# Connectors.net
KiCad netlist of a schematic drawn in Altium Designer
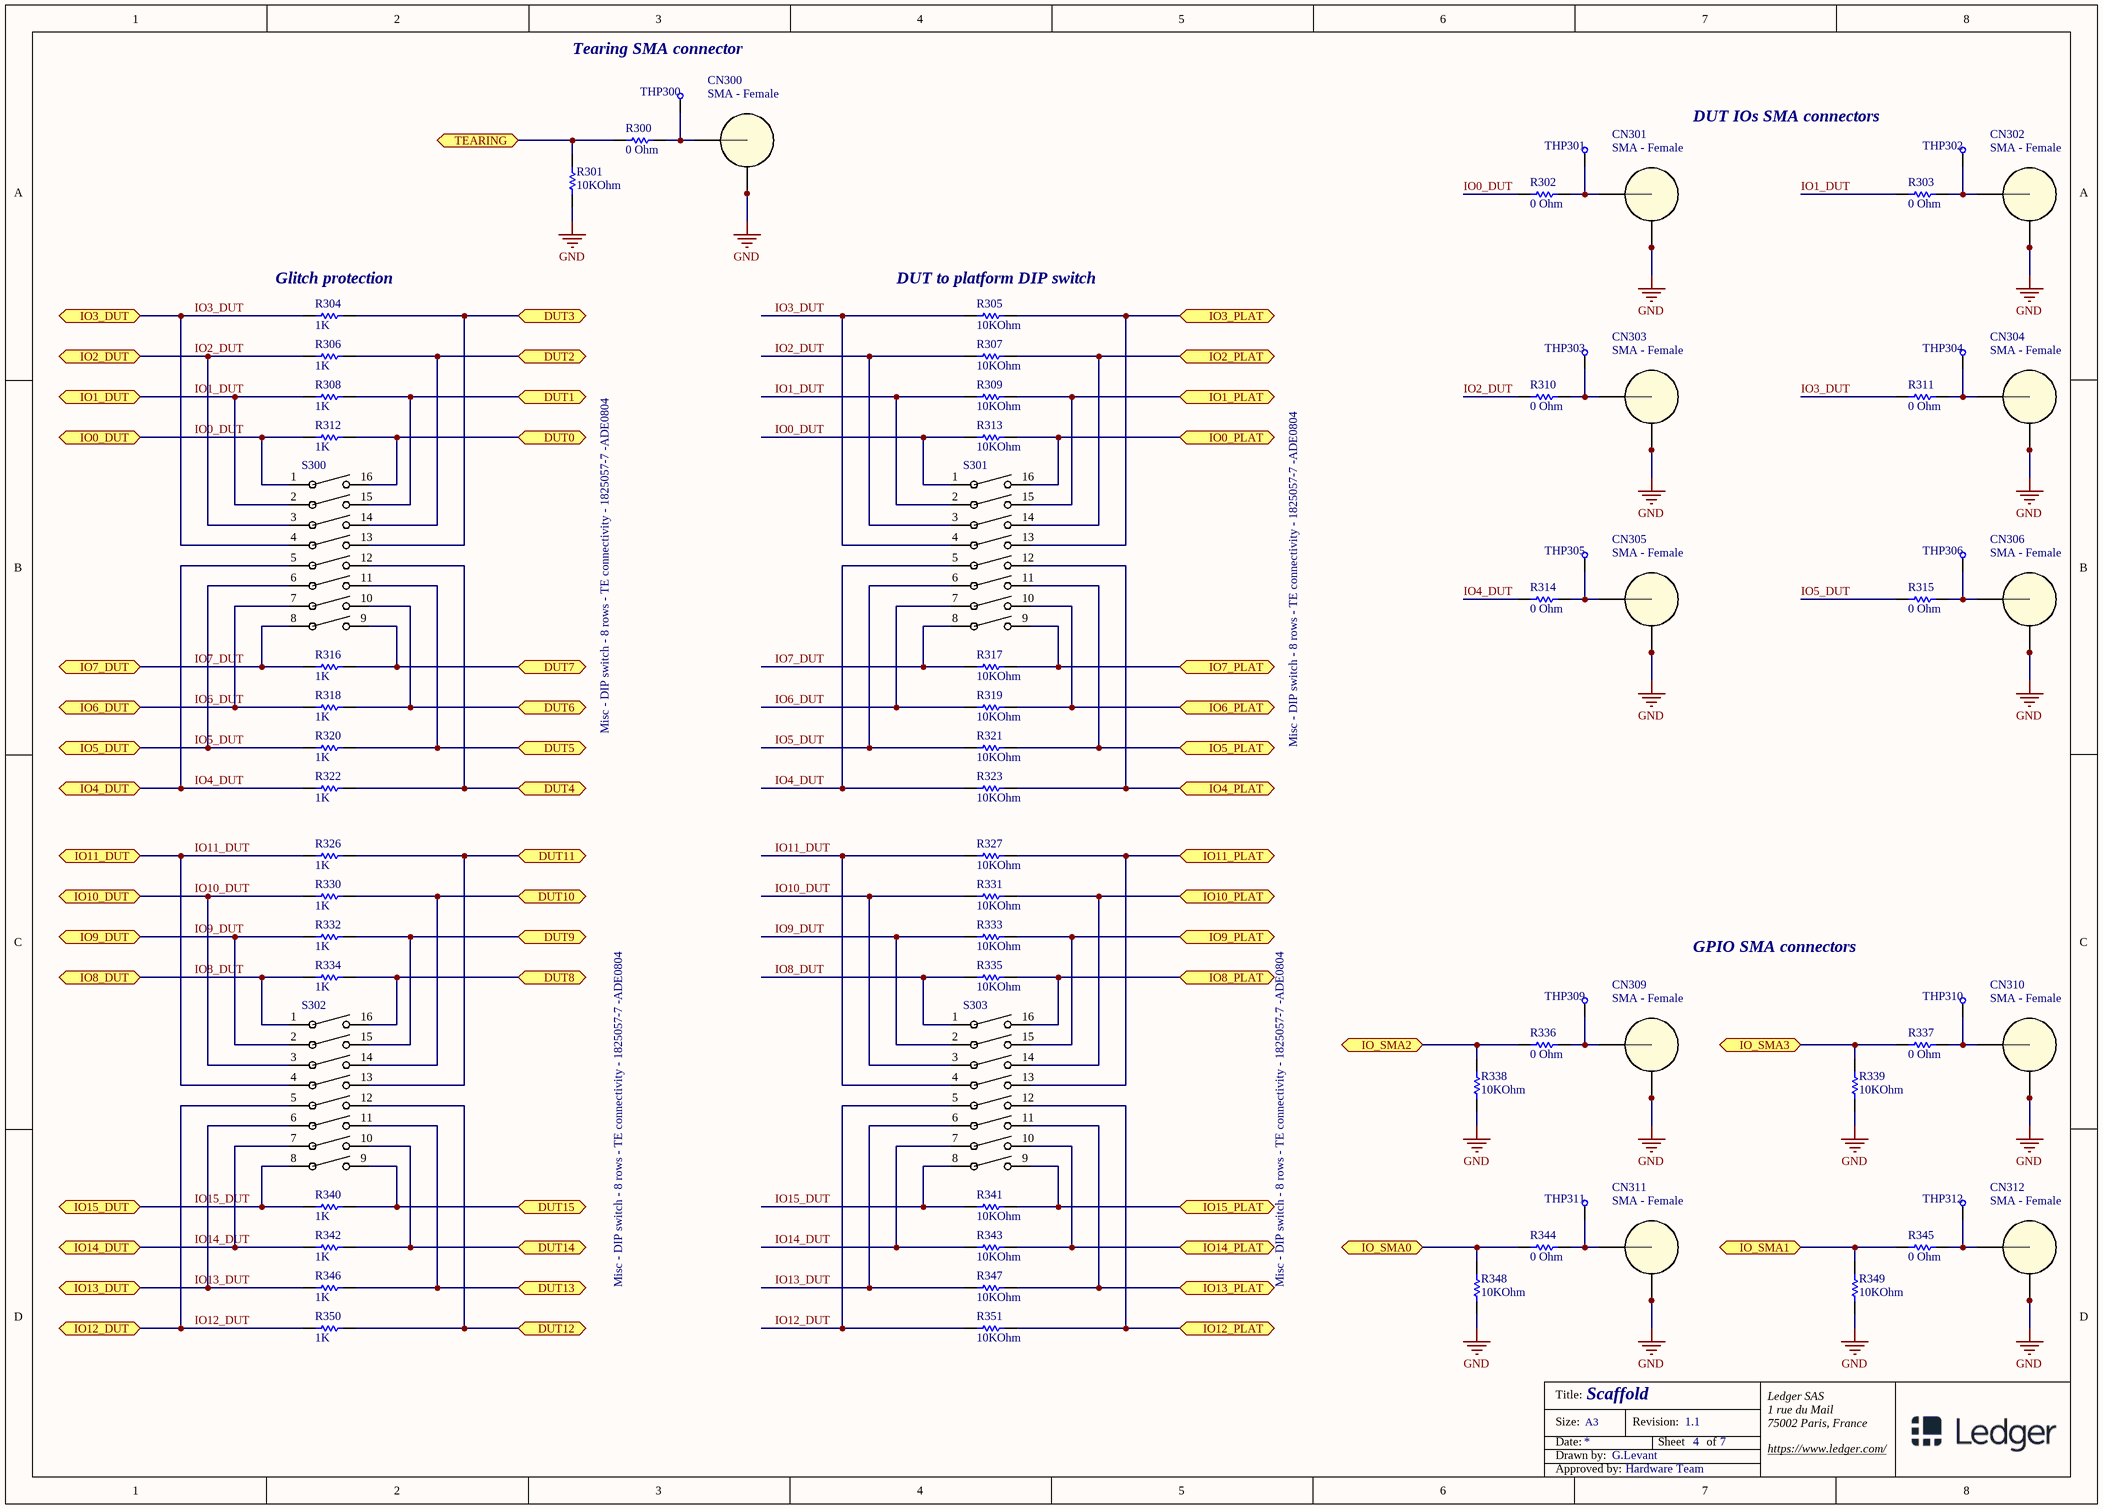
[diagram p0: Connectors.SchDoc]

(export (version "E")
  (design (tool "Eeschema 10.0.6"))
  (components
    (comp (ref "CN300")
      (value "SMA - Female")
      (footprint "SAMTEC_SMA-J-P-X-ST-EM3")
      (description "Connector - SMA - Female - Horizontal - Mid Mount - Samtec - SMA–J–P–H–ST–EM3")
      (fields (field (name "MANUFACTURER") "Samtec"))
      (libsource (lib "Ledger_Dev") (part "Connector - SMA - Female - Horizontal - Mid Mount - Samtec - SMA–J–P–H–ST–EM3"))
    )
    (comp (ref "CN301")
      (value "SMA - Female")
      (footprint "SAMTEC_SMA-J-P-X-ST-EM3")
      (description "Connector - SMA - Female - Horizontal - Mid Mount - Samtec - SMA–J–P–H–ST–EM3")
      (fields (field (name "MANUFACTURER") "Samtec"))
      (libsource (lib "Ledger_Dev") (part "Connector - SMA - Female - Horizontal - Mid Mount - Samtec - SMA–J–P–H–ST–EM3"))
    )
    (comp (ref "CN302")
      (value "SMA - Female")
      (footprint "SAMTEC_SMA-J-P-X-ST-EM3")
      (description "Connector - SMA - Female - Horizontal - Mid Mount - Samtec - SMA–J–P–H–ST–EM3")
      (fields (field (name "MANUFACTURER") "Samtec"))
      (libsource (lib "Ledger_Dev") (part "Connector - SMA - Female - Horizontal - Mid Mount - Samtec - SMA–J–P–H–ST–EM3"))
    )
    (comp (ref "CN303")
      (value "SMA - Female")
      (footprint "SAMTEC_SMA-J-P-X-ST-EM3")
      (description "Connector - SMA - Female - Horizontal - Mid Mount - Samtec - SMA–J–P–H–ST–EM3")
      (fields (field (name "MANUFACTURER") "Samtec"))
      (libsource (lib "Ledger_Dev") (part "Connector - SMA - Female - Horizontal - Mid Mount - Samtec - SMA–J–P–H–ST–EM3"))
    )
    (comp (ref "CN304")
      (value "SMA - Female")
      (footprint "SAMTEC_SMA-J-P-X-ST-EM3")
      (description "Connector - SMA - Female - Horizontal - Mid Mount - Samtec - SMA–J–P–H–ST–EM3")
      (fields (field (name "MANUFACTURER") "Samtec"))
      (libsource (lib "Ledger_Dev") (part "Connector - SMA - Female - Horizontal - Mid Mount - Samtec - SMA–J–P–H–ST–EM3"))
    )
    (comp (ref "CN305")
      (value "SMA - Female")
      (footprint "SAMTEC_SMA-J-P-X-ST-EM3")
      (description "Connector - SMA - Female - Horizontal - Mid Mount - Samtec - SMA–J–P–H–ST–EM3")
      (fields (field (name "MANUFACTURER") "Samtec"))
      (libsource (lib "Ledger_Dev") (part "Connector - SMA - Female - Horizontal - Mid Mount - Samtec - SMA–J–P–H–ST–EM3"))
    )
    (comp (ref "CN306")
      (value "SMA - Female")
      (footprint "SAMTEC_SMA-J-P-X-ST-EM3")
      (description "Connector - SMA - Female - Horizontal - Mid Mount - Samtec - SMA–J–P–H–ST–EM3")
      (fields (field (name "MANUFACTURER") "Samtec"))
      (libsource (lib "Ledger_Dev") (part "Connector - SMA - Female - Horizontal - Mid Mount - Samtec - SMA–J–P–H–ST–EM3"))
    )
    (comp (ref "CN309")
      (value "SMA - Female")
      (footprint "SAMTEC_SMA-J-P-X-ST-EM3")
      (description "Connector - SMA - Female - Horizontal - Mid Mount - Samtec - SMA–J–P–H–ST–EM3")
      (fields (field (name "MANUFACTURER") "Samtec"))
      (libsource (lib "Ledger_Dev") (part "Connector - SMA - Female - Horizontal - Mid Mount - Samtec - SMA–J–P–H–ST–EM3"))
    )
    (comp (ref "CN310")
      (value "SMA - Female")
      (footprint "SAMTEC_SMA-J-P-X-ST-EM3")
      (description "Connector - SMA - Female - Horizontal - Mid Mount - Samtec - SMA–J–P–H–ST–EM3")
      (fields (field (name "MANUFACTURER") "Samtec"))
      (libsource (lib "Ledger_Dev") (part "Connector - SMA - Female - Horizontal - Mid Mount - Samtec - SMA–J–P–H–ST–EM3"))
    )
    (comp (ref "CN311")
      (value "SMA - Female")
      (footprint "SAMTEC_SMA-J-P-X-ST-EM3")
      (description "Connector - SMA - Female - Horizontal - Mid Mount - Samtec - SMA–J–P–H–ST–EM3")
      (fields (field (name "MANUFACTURER") "Samtec"))
      (libsource (lib "Ledger_Dev") (part "Connector - SMA - Female - Horizontal - Mid Mount - Samtec - SMA–J–P–H–ST–EM3"))
    )
    (comp (ref "CN312")
      (value "SMA - Female")
      (footprint "SAMTEC_SMA-J-P-X-ST-EM3")
      (description "Connector - SMA - Female - Horizontal - Mid Mount - Samtec - SMA–J–P–H–ST–EM3")
      (fields (field (name "MANUFACTURER") "Samtec"))
      (libsource (lib "Ledger_Dev") (part "Connector - SMA - Female - Horizontal - Mid Mount - Samtec - SMA–J–P–H–ST–EM3"))
    )
    (comp (ref "R300")
      (value "0 Ohm")
      (footprint "RES0603")
      (description "Resistor 0603 - 0Ohm - 1/10W - 1%")
      (fields (field (name "POWER") "1/10W") (field (name "TOLERANCE") "1%"))
      (libsource (lib "Ledger_Prod") (part "Resistor 0603 -        0Ohm - 1/10W - 1%"))
    )
    (comp (ref "R301")
      (value "10KOhm")
      (footprint "RES0603")
      (description "Resistor 0603 -    10KOhm - 1/10W - 1%")
      (fields (field (name "TOLERANCE") "1%") (field (name "POWER") "1/10W"))
      (libsource (lib "Ledger_Prod") (part "Resistor 0603 -    10KOhm - 1/10W - 1%"))
    )
    (comp (ref "R302")
      (value "0 Ohm")
      (footprint "RES0603")
      (description "Resistor 0603 - 0Ohm - 1/10W - 1%")
      (fields (field (name "POWER") "1/10W") (field (name "TOLERANCE") "1%"))
      (libsource (lib "Ledger_Prod") (part "Resistor 0603 -        0Ohm - 1/10W - 1%"))
    )
    (comp (ref "R303")
      (value "0 Ohm")
      (footprint "RES0603")
      (description "Resistor 0603 - 0Ohm - 1/10W - 1%")
      (fields (field (name "POWER") "1/10W") (field (name "TOLERANCE") "1%"))
      (libsource (lib "Ledger_Prod") (part "Resistor 0603 -        0Ohm - 1/10W - 1%"))
    )
    (comp (ref "R304")
      (value "1K")
      (footprint "RES0603")
      (description "Resistor 0603 - 1KOhm - 1/10W - 1%")
      (fields (field (name "TOLERANCE") "1%") (field (name "POWER") "1/10W"))
      (libsource (lib "Ledger_Prod") (part "Resistor 0603 -      1KOhm - 1/10W - 1%"))
    )
    (comp (ref "R305")
      (value "10KOhm")
      (footprint "RES0603")
      (description "Resistor 0603 -    10KOhm - 1/10W - 1%")
      (fields (field (name "TOLERANCE") "1%") (field (name "POWER") "1/10W"))
      (libsource (lib "Ledger_Prod") (part "Resistor 0603 -    10KOhm - 1/10W - 1%"))
    )
    (comp (ref "R306")
      (value "1K")
      (footprint "RES0603")
      (description "Resistor 0603 - 1KOhm - 1/10W - 1%")
      (fields (field (name "TOLERANCE") "1%") (field (name "POWER") "1/10W"))
      (libsource (lib "Ledger_Prod") (part "Resistor 0603 -      1KOhm - 1/10W - 1%"))
    )
    (comp (ref "R307")
      (value "10KOhm")
      (footprint "RES0603")
      (description "Resistor 0603 -    10KOhm - 1/10W - 1%")
      (fields (field (name "TOLERANCE") "1%") (field (name "POWER") "1/10W"))
      (libsource (lib "Ledger_Prod") (part "Resistor 0603 -    10KOhm - 1/10W - 1%"))
    )
    (comp (ref "R308")
      (value "1K")
      (footprint "RES0603")
      (description "Resistor 0603 - 1KOhm - 1/10W - 1%")
      (fields (field (name "TOLERANCE") "1%") (field (name "POWER") "1/10W"))
      (libsource (lib "Ledger_Prod") (part "Resistor 0603 -      1KOhm - 1/10W - 1%"))
    )
    (comp (ref "R309")
      (value "10KOhm")
      (footprint "RES0603")
      (description "Resistor 0603 -    10KOhm - 1/10W - 1%")
      (fields (field (name "TOLERANCE") "1%") (field (name "POWER") "1/10W"))
      (libsource (lib "Ledger_Prod") (part "Resistor 0603 -    10KOhm - 1/10W - 1%"))
    )
    (comp (ref "R310")
      (value "0 Ohm")
      (footprint "RES0603")
      (description "Resistor 0603 - 0Ohm - 1/10W - 1%")
      (fields (field (name "POWER") "1/10W") (field (name "TOLERANCE") "1%"))
      (libsource (lib "Ledger_Prod") (part "Resistor 0603 -        0Ohm - 1/10W - 1%"))
    )
    (comp (ref "R311")
      (value "0 Ohm")
      (footprint "RES0603")
      (description "Resistor 0603 - 0Ohm - 1/10W - 1%")
      (fields (field (name "POWER") "1/10W") (field (name "TOLERANCE") "1%"))
      (libsource (lib "Ledger_Prod") (part "Resistor 0603 -        0Ohm - 1/10W - 1%"))
    )
    (comp (ref "R312")
      (value "1K")
      (footprint "RES0603")
      (description "Resistor 0603 - 1KOhm - 1/10W - 1%")
      (fields (field (name "TOLERANCE") "1%") (field (name "POWER") "1/10W"))
      (libsource (lib "Ledger_Prod") (part "Resistor 0603 -      1KOhm - 1/10W - 1%"))
    )
    (comp (ref "R313")
      (value "10KOhm")
      (footprint "RES0603")
      (description "Resistor 0603 -    10KOhm - 1/10W - 1%")
      (fields (field (name "TOLERANCE") "1%") (field (name "POWER") "1/10W"))
      (libsource (lib "Ledger_Prod") (part "Resistor 0603 -    10KOhm - 1/10W - 1%"))
    )
    (comp (ref "R314")
      (value "0 Ohm")
      (footprint "RES0603")
      (description "Resistor 0603 - 0Ohm - 1/10W - 1%")
      (fields (field (name "POWER") "1/10W") (field (name "TOLERANCE") "1%"))
      (libsource (lib "Ledger_Prod") (part "Resistor 0603 -        0Ohm - 1/10W - 1%"))
    )
    (comp (ref "R315")
      (value "0 Ohm")
      (footprint "RES0603")
      (description "Resistor 0603 - 0Ohm - 1/10W - 1%")
      (fields (field (name "POWER") "1/10W") (field (name "TOLERANCE") "1%"))
      (libsource (lib "Ledger_Prod") (part "Resistor 0603 -        0Ohm - 1/10W - 1%"))
    )
    (comp (ref "R316")
      (value "1K")
      (footprint "RES0603")
      (description "Resistor 0603 - 1KOhm - 1/10W - 1%")
      (fields (field (name "TOLERANCE") "1%") (field (name "POWER") "1/10W"))
      (libsource (lib "Ledger_Prod") (part "Resistor 0603 -      1KOhm - 1/10W - 1%"))
    )
    (comp (ref "R317")
      (value "10KOhm")
      (footprint "RES0603")
      (description "Resistor 0603 -    10KOhm - 1/10W - 1%")
      (fields (field (name "TOLERANCE") "1%") (field (name "POWER") "1/10W"))
      (libsource (lib "Ledger_Prod") (part "Resistor 0603 -    10KOhm - 1/10W - 1%"))
    )
    (comp (ref "R318")
      (value "1K")
      (footprint "RES0603")
      (description "Resistor 0603 - 1KOhm - 1/10W - 1%")
      (fields (field (name "TOLERANCE") "1%") (field (name "POWER") "1/10W"))
      (libsource (lib "Ledger_Prod") (part "Resistor 0603 -      1KOhm - 1/10W - 1%"))
    )
    (comp (ref "R319")
      (value "10KOhm")
      (footprint "RES0603")
      (description "Resistor 0603 -    10KOhm - 1/10W - 1%")
      (fields (field (name "TOLERANCE") "1%") (field (name "POWER") "1/10W"))
      (libsource (lib "Ledger_Prod") (part "Resistor 0603 -    10KOhm - 1/10W - 1%"))
    )
    (comp (ref "R320")
      (value "1K")
      (footprint "RES0603")
      (description "Resistor 0603 - 1KOhm - 1/10W - 1%")
      (fields (field (name "TOLERANCE") "1%") (field (name "POWER") "1/10W"))
      (libsource (lib "Ledger_Prod") (part "Resistor 0603 -      1KOhm - 1/10W - 1%"))
    )
    (comp (ref "R321")
      (value "10KOhm")
      (footprint "RES0603")
      (description "Resistor 0603 -    10KOhm - 1/10W - 1%")
      (fields (field (name "TOLERANCE") "1%") (field (name "POWER") "1/10W"))
      (libsource (lib "Ledger_Prod") (part "Resistor 0603 -    10KOhm - 1/10W - 1%"))
    )
    (comp (ref "R322")
      (value "1K")
      (footprint "RES0603")
      (description "Resistor 0603 - 1KOhm - 1/10W - 1%")
      (fields (field (name "TOLERANCE") "1%") (field (name "POWER") "1/10W"))
      (libsource (lib "Ledger_Prod") (part "Resistor 0603 -      1KOhm - 1/10W - 1%"))
    )
    (comp (ref "R323")
      (value "10KOhm")
      (footprint "RES0603")
      (description "Resistor 0603 -    10KOhm - 1/10W - 1%")
      (fields (field (name "TOLERANCE") "1%") (field (name "POWER") "1/10W"))
      (libsource (lib "Ledger_Prod") (part "Resistor 0603 -    10KOhm - 1/10W - 1%"))
    )
    (comp (ref "R326")
      (value "1K")
      (footprint "RES0603")
      (description "Resistor 0603 - 1KOhm - 1/10W - 1%")
      (fields (field (name "TOLERANCE") "1%") (field (name "POWER") "1/10W"))
      (libsource (lib "Ledger_Prod") (part "Resistor 0603 -      1KOhm - 1/10W - 1%"))
    )
    (comp (ref "R327")
      (value "10KOhm")
      (footprint "RES0603")
      (description "Resistor 0603 -    10KOhm - 1/10W - 1%")
      (fields (field (name "TOLERANCE") "1%") (field (name "POWER") "1/10W"))
      (libsource (lib "Ledger_Prod") (part "Resistor 0603 -    10KOhm - 1/10W - 1%"))
    )
    (comp (ref "R330")
      (value "1K")
      (footprint "RES0603")
      (description "Resistor 0603 - 1KOhm - 1/10W - 1%")
      (fields (field (name "TOLERANCE") "1%") (field (name "POWER") "1/10W"))
      (libsource (lib "Ledger_Prod") (part "Resistor 0603 -      1KOhm - 1/10W - 1%"))
    )
    (comp (ref "R331")
      (value "10KOhm")
      (footprint "RES0603")
      (description "Resistor 0603 -    10KOhm - 1/10W - 1%")
      (fields (field (name "TOLERANCE") "1%") (field (name "POWER") "1/10W"))
      (libsource (lib "Ledger_Prod") (part "Resistor 0603 -    10KOhm - 1/10W - 1%"))
    )
    (comp (ref "R332")
      (value "1K")
      (footprint "RES0603")
      (description "Resistor 0603 - 1KOhm - 1/10W - 1%")
      (fields (field (name "TOLERANCE") "1%") (field (name "POWER") "1/10W"))
      (libsource (lib "Ledger_Prod") (part "Resistor 0603 -      1KOhm - 1/10W - 1%"))
    )
    (comp (ref "R333")
      (value "10KOhm")
      (footprint "RES0603")
      (description "Resistor 0603 -    10KOhm - 1/10W - 1%")
      (fields (field (name "TOLERANCE") "1%") (field (name "POWER") "1/10W"))
      (libsource (lib "Ledger_Prod") (part "Resistor 0603 -    10KOhm - 1/10W - 1%"))
    )
    (comp (ref "R334")
      (value "1K")
      (footprint "RES0603")
      (description "Resistor 0603 - 1KOhm - 1/10W - 1%")
      (fields (field (name "TOLERANCE") "1%") (field (name "POWER") "1/10W"))
      (libsource (lib "Ledger_Prod") (part "Resistor 0603 -      1KOhm - 1/10W - 1%"))
    )
    (comp (ref "R335")
      (value "10KOhm")
      (footprint "RES0603")
      (description "Resistor 0603 -    10KOhm - 1/10W - 1%")
      (fields (field (name "TOLERANCE") "1%") (field (name "POWER") "1/10W"))
      (libsource (lib "Ledger_Prod") (part "Resistor 0603 -    10KOhm - 1/10W - 1%"))
    )
    (comp (ref "R336")
      (value "0 Ohm")
      (footprint "RES0603")
      (description "Resistor 0603 - 0Ohm - 1/10W - 1%")
      (fields (field (name "POWER") "1/10W") (field (name "TOLERANCE") "1%"))
      (libsource (lib "Ledger_Prod") (part "Resistor 0603 -        0Ohm - 1/10W - 1%"))
    )
    (comp (ref "R337")
      (value "0 Ohm")
      (footprint "RES0603")
      (description "Resistor 0603 - 0Ohm - 1/10W - 1%")
      (fields (field (name "POWER") "1/10W") (field (name "TOLERANCE") "1%"))
      (libsource (lib "Ledger_Prod") (part "Resistor 0603 -        0Ohm - 1/10W - 1%"))
    )
    (comp (ref "R338")
      (value "10KOhm")
      (footprint "RES0603")
      (description "Resistor 0603 -    10KOhm - 1/10W - 1%")
      (fields (field (name "TOLERANCE") "1%") (field (name "POWER") "1/10W"))
      (libsource (lib "Ledger_Prod") (part "Resistor 0603 -    10KOhm - 1/10W - 1%"))
    )
    (comp (ref "R339")
      (value "10KOhm")
      (footprint "RES0603")
      (description "Resistor 0603 -    10KOhm - 1/10W - 1%")
      (fields (field (name "TOLERANCE") "1%") (field (name "POWER") "1/10W"))
      (libsource (lib "Ledger_Prod") (part "Resistor 0603 -    10KOhm - 1/10W - 1%"))
    )
    (comp (ref "R340")
      (value "1K")
      (footprint "RES0603")
      (description "Resistor 0603 - 1KOhm - 1/10W - 1%")
      (fields (field (name "TOLERANCE") "1%") (field (name "POWER") "1/10W"))
      (libsource (lib "Ledger_Prod") (part "Resistor 0603 -      1KOhm - 1/10W - 1%"))
    )
    (comp (ref "R341")
      (value "10KOhm")
      (footprint "RES0603")
      (description "Resistor 0603 -    10KOhm - 1/10W - 1%")
      (fields (field (name "TOLERANCE") "1%") (field (name "POWER") "1/10W"))
      (libsource (lib "Ledger_Prod") (part "Resistor 0603 -    10KOhm - 1/10W - 1%"))
    )
    (comp (ref "R342")
      (value "1K")
      (footprint "RES0603")
      (description "Resistor 0603 - 1KOhm - 1/10W - 1%")
      (fields (field (name "TOLERANCE") "1%") (field (name "POWER") "1/10W"))
      (libsource (lib "Ledger_Prod") (part "Resistor 0603 -      1KOhm - 1/10W - 1%"))
    )
    (comp (ref "R343")
      (value "10KOhm")
      (footprint "RES0603")
      (description "Resistor 0603 -    10KOhm - 1/10W - 1%")
      (fields (field (name "TOLERANCE") "1%") (field (name "POWER") "1/10W"))
      (libsource (lib "Ledger_Prod") (part "Resistor 0603 -    10KOhm - 1/10W - 1%"))
    )
    (comp (ref "R344")
      (value "0 Ohm")
      (footprint "RES0603")
      (description "Resistor 0603 - 0Ohm - 1/10W - 1%")
      (fields (field (name "POWER") "1/10W") (field (name "TOLERANCE") "1%"))
      (libsource (lib "Ledger_Prod") (part "Resistor 0603 -        0Ohm - 1/10W - 1%"))
    )
    (comp (ref "R345")
      (value "0 Ohm")
      (footprint "RES0603")
      (description "Resistor 0603 - 0Ohm - 1/10W - 1%")
      (fields (field (name "POWER") "1/10W") (field (name "TOLERANCE") "1%"))
      (libsource (lib "Ledger_Prod") (part "Resistor 0603 -        0Ohm - 1/10W - 1%"))
    )
    (comp (ref "R346")
      (value "1K")
      (footprint "RES0603")
      (description "Resistor 0603 - 1KOhm - 1/10W - 1%")
      (fields (field (name "TOLERANCE") "1%") (field (name "POWER") "1/10W"))
      (libsource (lib "Ledger_Prod") (part "Resistor 0603 -      1KOhm - 1/10W - 1%"))
    )
    (comp (ref "R347")
      (value "10KOhm")
      (footprint "RES0603")
      (description "Resistor 0603 -    10KOhm - 1/10W - 1%")
      (fields (field (name "TOLERANCE") "1%") (field (name "POWER") "1/10W"))
      (libsource (lib "Ledger_Prod") (part "Resistor 0603 -    10KOhm - 1/10W - 1%"))
    )
    (comp (ref "R348")
      (value "10KOhm")
      (footprint "RES0603")
      (description "Resistor 0603 -    10KOhm - 1/10W - 1%")
      (fields (field (name "TOLERANCE") "1%") (field (name "POWER") "1/10W"))
      (libsource (lib "Ledger_Prod") (part "Resistor 0603 -    10KOhm - 1/10W - 1%"))
    )
    (comp (ref "R349")
      (value "10KOhm")
      (footprint "RES0603")
      (description "Resistor 0603 -    10KOhm - 1/10W - 1%")
      (fields (field (name "TOLERANCE") "1%") (field (name "POWER") "1/10W"))
      (libsource (lib "Ledger_Prod") (part "Resistor 0603 -    10KOhm - 1/10W - 1%"))
    )
    (comp (ref "R350")
      (value "1K")
      (footprint "RES0603")
      (description "Resistor 0603 - 1KOhm - 1/10W - 1%")
      (fields (field (name "TOLERANCE") "1%") (field (name "POWER") "1/10W"))
      (libsource (lib "Ledger_Prod") (part "Resistor 0603 -      1KOhm - 1/10W - 1%"))
    )
    (comp (ref "R351")
      (value "10KOhm")
      (footprint "RES0603")
      (description "Resistor 0603 -    10KOhm - 1/10W - 1%")
      (fields (field (name "TOLERANCE") "1%") (field (name "POWER") "1/10W"))
      (libsource (lib "Ledger_Prod") (part "Resistor 0603 -    10KOhm - 1/10W - 1%"))
    )
    (comp (ref "S300")
      (value "Misc - DIP switch - 8 rows - TE connectivity - 1825057-7 -ADE0804")
      (footprint "SWDIP16_300X3.51")
      (description "Misc - DIP switch - 8 rows - TE connectivity - 1825057-7")
      (fields (field (name "MANUFACTURER") "TE Connectivity"))
      (libsource (lib "Ledger_Dev") (part "Misc - DIP switch - 8 rows - TE connectivity - 1825057-7 -ADE0804"))
    )
    (comp (ref "S301")
      (value "Misc - DIP switch - 8 rows - TE connectivity - 1825057-7 -ADE0804")
      (footprint "SWDIP16_300X3.51")
      (description "Misc - DIP switch - 8 rows - TE connectivity - 1825057-7")
      (fields (field (name "MANUFACTURER") "TE Connectivity"))
      (libsource (lib "Ledger_Dev") (part "Misc - DIP switch - 8 rows - TE connectivity - 1825057-7 -ADE0804"))
    )
    (comp (ref "S302")
      (value "Misc - DIP switch - 8 rows - TE connectivity - 1825057-7 -ADE0804")
      (footprint "SWDIP16_300X3.51")
      (description "Misc - DIP switch - 8 rows - TE connectivity - 1825057-7")
      (fields (field (name "MANUFACTURER") "TE Connectivity"))
      (libsource (lib "Ledger_Dev") (part "Misc - DIP switch - 8 rows - TE connectivity - 1825057-7 -ADE0804"))
    )
    (comp (ref "S303")
      (value "Misc - DIP switch - 8 rows - TE connectivity - 1825057-7 -ADE0804")
      (footprint "SWDIP16_300X3.51")
      (description "Misc - DIP switch - 8 rows - TE connectivity - 1825057-7")
      (fields (field (name "MANUFACTURER") "TE Connectivity"))
      (libsource (lib "Ledger_Dev") (part "Misc - DIP switch - 8 rows - TE connectivity - 1825057-7 -ADE0804"))
    )
    (comp (ref "THP300")
      (value "Misc - Test pin - Through hole - Millmax - 6821-0-00-15-00-00-08-0")
      (footprint "MILLMAX_6821-0-00-15-00-00-08-0")
      (fields (field (name "MANUFACTURER") "Mill-max"))
      (libsource (lib "Ledger_Dev") (part "Misc - Test pin - Through hole - Millmax - 6821-0-00-15-00-00-08-0"))
    )
    (comp (ref "THP301")
      (value "Misc - Test pin - Through hole - Millmax - 6821-0-00-15-00-00-08-0")
      (footprint "MILLMAX_6821-0-00-15-00-00-08-0")
      (fields (field (name "MANUFACTURER") "Mill-max"))
      (libsource (lib "Ledger_Dev") (part "Misc - Test pin - Through hole - Millmax - 6821-0-00-15-00-00-08-0"))
    )
    (comp (ref "THP302")
      (value "Misc - Test pin - Through hole - Millmax - 6821-0-00-15-00-00-08-0")
      (footprint "MILLMAX_6821-0-00-15-00-00-08-0")
      (fields (field (name "MANUFACTURER") "Mill-max"))
      (libsource (lib "Ledger_Dev") (part "Misc - Test pin - Through hole - Millmax - 6821-0-00-15-00-00-08-0"))
    )
    (comp (ref "THP303")
      (value "Misc - Test pin - Through hole - Millmax - 6821-0-00-15-00-00-08-0")
      (footprint "MILLMAX_6821-0-00-15-00-00-08-0")
      (fields (field (name "MANUFACTURER") "Mill-max"))
      (libsource (lib "Ledger_Dev") (part "Misc - Test pin - Through hole - Millmax - 6821-0-00-15-00-00-08-0"))
    )
    (comp (ref "THP304")
      (value "Misc - Test pin - Through hole - Millmax - 6821-0-00-15-00-00-08-0")
      (footprint "MILLMAX_6821-0-00-15-00-00-08-0")
      (fields (field (name "MANUFACTURER") "Mill-max"))
      (libsource (lib "Ledger_Dev") (part "Misc - Test pin - Through hole - Millmax - 6821-0-00-15-00-00-08-0"))
    )
    (comp (ref "THP305")
      (value "Misc - Test pin - Through hole - Millmax - 6821-0-00-15-00-00-08-0")
      (footprint "MILLMAX_6821-0-00-15-00-00-08-0")
      (fields (field (name "MANUFACTURER") "Mill-max"))
      (libsource (lib "Ledger_Dev") (part "Misc - Test pin - Through hole - Millmax - 6821-0-00-15-00-00-08-0"))
    )
    (comp (ref "THP306")
      (value "Misc - Test pin - Through hole - Millmax - 6821-0-00-15-00-00-08-0")
      (footprint "MILLMAX_6821-0-00-15-00-00-08-0")
      (fields (field (name "MANUFACTURER") "Mill-max"))
      (libsource (lib "Ledger_Dev") (part "Misc - Test pin - Through hole - Millmax - 6821-0-00-15-00-00-08-0"))
    )
    (comp (ref "THP309")
      (value "Misc - Test pin - Through hole - Millmax - 6821-0-00-15-00-00-08-0")
      (footprint "MILLMAX_6821-0-00-15-00-00-08-0")
      (fields (field (name "MANUFACTURER") "Mill-max"))
      (libsource (lib "Ledger_Dev") (part "Misc - Test pin - Through hole - Millmax - 6821-0-00-15-00-00-08-0"))
    )
    (comp (ref "THP310")
      (value "Misc - Test pin - Through hole - Millmax - 6821-0-00-15-00-00-08-0")
      (footprint "MILLMAX_6821-0-00-15-00-00-08-0")
      (fields (field (name "MANUFACTURER") "Mill-max"))
      (libsource (lib "Ledger_Dev") (part "Misc - Test pin - Through hole - Millmax - 6821-0-00-15-00-00-08-0"))
    )
    (comp (ref "THP311")
      (value "Misc - Test pin - Through hole - Millmax - 6821-0-00-15-00-00-08-0")
      (footprint "MILLMAX_6821-0-00-15-00-00-08-0")
      (fields (field (name "MANUFACTURER") "Mill-max"))
      (libsource (lib "Ledger_Dev") (part "Misc - Test pin - Through hole - Millmax - 6821-0-00-15-00-00-08-0"))
    )
    (comp (ref "THP312")
      (value "Misc - Test pin - Through hole - Millmax - 6821-0-00-15-00-00-08-0")
      (footprint "MILLMAX_6821-0-00-15-00-00-08-0")
      (fields (field (name "MANUFACTURER") "Mill-max"))
      (libsource (lib "Ledger_Dev") (part "Misc - Test pin - Through hole - Millmax - 6821-0-00-15-00-00-08-0"))
    )
  )
  (nets
    (net (code "1") (name "/DUT0") (class "Default")
      (node (ref "R312") (pin "2") (pinfunction "2_2") (pintype "passive"))
      (node (ref "S300") (pin "16") (pinfunction "16_16") (pintype "passive"))
    )
    (net (code "2") (name "/DUT1") (class "Default")
      (node (ref "R308") (pin "2") (pinfunction "2_2") (pintype "passive"))
      (node (ref "S300") (pin "15") (pinfunction "15_15") (pintype "passive"))
    )
    (net (code "3") (name "/DUT2") (class "Default")
      (node (ref "R306") (pin "2") (pinfunction "2_2") (pintype "passive"))
      (node (ref "S300") (pin "14") (pinfunction "14_14") (pintype "passive"))
    )
    (net (code "4") (name "/DUT3") (class "Default")
      (node (ref "R304") (pin "2") (pinfunction "2_2") (pintype "passive"))
      (node (ref "S300") (pin "13") (pinfunction "13_13") (pintype "passive"))
    )
    (net (code "5") (name "/DUT4") (class "Default")
      (node (ref "R322") (pin "2") (pinfunction "2_2") (pintype "passive"))
      (node (ref "S300") (pin "12") (pinfunction "12_12") (pintype "passive"))
    )
    (net (code "6") (name "/DUT5") (class "Default")
      (node (ref "R320") (pin "2") (pinfunction "2_2") (pintype "passive"))
      (node (ref "S300") (pin "11") (pinfunction "11_11") (pintype "passive"))
    )
    (net (code "7") (name "/DUT6") (class "Default")
      (node (ref "R318") (pin "2") (pinfunction "2_2") (pintype "passive"))
      (node (ref "S300") (pin "10") (pinfunction "10_10") (pintype "passive"))
    )
    (net (code "8") (name "/DUT7") (class "Default")
      (node (ref "R316") (pin "2") (pinfunction "2_2") (pintype "passive"))
      (node (ref "S300") (pin "9") (pinfunction "9_9") (pintype "passive"))
    )
    (net (code "9") (name "/DUT8") (class "Default")
      (node (ref "R334") (pin "2") (pinfunction "2_2") (pintype "passive"))
      (node (ref "S302") (pin "16") (pinfunction "16_16") (pintype "passive"))
    )
    (net (code "10") (name "/DUT9") (class "Default")
      (node (ref "R332") (pin "2") (pinfunction "2_2") (pintype "passive"))
      (node (ref "S302") (pin "15") (pinfunction "15_15") (pintype "passive"))
    )
    (net (code "11") (name "/DUT10") (class "Default")
      (node (ref "R330") (pin "2") (pinfunction "2_2") (pintype "passive"))
      (node (ref "S302") (pin "14") (pinfunction "14_14") (pintype "passive"))
    )
    (net (code "12") (name "/DUT11") (class "Default")
      (node (ref "R326") (pin "2") (pinfunction "2_2") (pintype "passive"))
      (node (ref "S302") (pin "13") (pinfunction "13_13") (pintype "passive"))
    )
    (net (code "13") (name "/DUT12") (class "Default")
      (node (ref "R350") (pin "2") (pinfunction "2_2") (pintype "passive"))
      (node (ref "S302") (pin "12") (pinfunction "12_12") (pintype "passive"))
    )
    (net (code "14") (name "/DUT13") (class "Default")
      (node (ref "R346") (pin "2") (pinfunction "2_2") (pintype "passive"))
      (node (ref "S302") (pin "11") (pinfunction "11_11") (pintype "passive"))
    )
    (net (code "15") (name "/DUT14") (class "Default")
      (node (ref "R342") (pin "2") (pinfunction "2_2") (pintype "passive"))
      (node (ref "S302") (pin "10") (pinfunction "10_10") (pintype "passive"))
    )
    (net (code "16") (name "/DUT15") (class "Default")
      (node (ref "R340") (pin "2") (pinfunction "2_2") (pintype "passive"))
      (node (ref "S302") (pin "9") (pinfunction "9_9") (pintype "passive"))
    )
    (net (code "17") (name "/IO0_DUT") (class "Default")
      (node (ref "R302") (pin "1") (pinfunction "1_1") (pintype "passive"))
      (node (ref "R312") (pin "1") (pinfunction "1_1") (pintype "passive"))
      (node (ref "R313") (pin "1") (pinfunction "1_1") (pintype "passive"))
      (node (ref "S300") (pin "1") (pinfunction "1_1") (pintype "passive"))
      (node (ref "S301") (pin "1") (pinfunction "1_1") (pintype "passive"))
    )
    (net (code "18") (name "/IO0_PLAT") (class "Default")
      (node (ref "R313") (pin "2") (pinfunction "2_2") (pintype "passive"))
      (node (ref "S301") (pin "16") (pinfunction "16_16") (pintype "passive"))
    )
    (net (code "19") (name "/IO1_DUT") (class "Default")
      (node (ref "R303") (pin "1") (pinfunction "1_1") (pintype "passive"))
      (node (ref "R308") (pin "1") (pinfunction "1_1") (pintype "passive"))
      (node (ref "R309") (pin "1") (pinfunction "1_1") (pintype "passive"))
      (node (ref "S300") (pin "2") (pinfunction "2_2") (pintype "passive"))
      (node (ref "S301") (pin "2") (pinfunction "2_2") (pintype "passive"))
    )
    (net (code "20") (name "/IO1_PLAT") (class "Default")
      (node (ref "R309") (pin "2") (pinfunction "2_2") (pintype "passive"))
      (node (ref "S301") (pin "15") (pinfunction "15_15") (pintype "passive"))
    )
    (net (code "21") (name "/IO2_DUT") (class "Default")
      (node (ref "R306") (pin "1") (pinfunction "1_1") (pintype "passive"))
      (node (ref "R307") (pin "1") (pinfunction "1_1") (pintype "passive"))
      (node (ref "R310") (pin "1") (pinfunction "1_1") (pintype "passive"))
      (node (ref "S300") (pin "3") (pinfunction "3_3") (pintype "passive"))
      (node (ref "S301") (pin "3") (pinfunction "3_3") (pintype "passive"))
    )
    (net (code "22") (name "/IO2_PLAT") (class "Default")
      (node (ref "R307") (pin "2") (pinfunction "2_2") (pintype "passive"))
      (node (ref "S301") (pin "14") (pinfunction "14_14") (pintype "passive"))
    )
    (net (code "23") (name "/IO3_DUT") (class "Default")
      (node (ref "R304") (pin "1") (pinfunction "1_1") (pintype "passive"))
      (node (ref "R305") (pin "1") (pinfunction "1_1") (pintype "passive"))
      (node (ref "R311") (pin "1") (pinfunction "1_1") (pintype "passive"))
      (node (ref "S300") (pin "4") (pinfunction "4_4") (pintype "passive"))
      (node (ref "S301") (pin "4") (pinfunction "4_4") (pintype "passive"))
    )
    (net (code "24") (name "/IO3_PLAT") (class "Default")
      (node (ref "R305") (pin "2") (pinfunction "2_2") (pintype "passive"))
      (node (ref "S301") (pin "13") (pinfunction "13_13") (pintype "passive"))
    )
    (net (code "25") (name "/IO4_DUT") (class "Default")
      (node (ref "R314") (pin "1") (pinfunction "1_1") (pintype "passive"))
      (node (ref "R322") (pin "1") (pinfunction "1_1") (pintype "passive"))
      (node (ref "R323") (pin "1") (pinfunction "1_1") (pintype "passive"))
      (node (ref "S300") (pin "5") (pinfunction "5_5") (pintype "passive"))
      (node (ref "S301") (pin "5") (pinfunction "5_5") (pintype "passive"))
    )
    (net (code "26") (name "/IO4_PLAT") (class "Default")
      (node (ref "R323") (pin "2") (pinfunction "2_2") (pintype "passive"))
      (node (ref "S301") (pin "12") (pinfunction "12_12") (pintype "passive"))
    )
    (net (code "27") (name "/IO5_DUT") (class "Default")
      (node (ref "R315") (pin "1") (pinfunction "1_1") (pintype "passive"))
      (node (ref "R320") (pin "1") (pinfunction "1_1") (pintype "passive"))
      (node (ref "R321") (pin "1") (pinfunction "1_1") (pintype "passive"))
      (node (ref "S300") (pin "6") (pinfunction "6_6") (pintype "passive"))
      (node (ref "S301") (pin "6") (pinfunction "6_6") (pintype "passive"))
    )
    (net (code "28") (name "/IO5_PLAT") (class "Default")
      (node (ref "R321") (pin "2") (pinfunction "2_2") (pintype "passive"))
      (node (ref "S301") (pin "11") (pinfunction "11_11") (pintype "passive"))
    )
    (net (code "29") (name "/IO6_DUT") (class "Default")
      (node (ref "R318") (pin "1") (pinfunction "1_1") (pintype "passive"))
      (node (ref "R319") (pin "1") (pinfunction "1_1") (pintype "passive"))
      (node (ref "S300") (pin "7") (pinfunction "7_7") (pintype "passive"))
      (node (ref "S301") (pin "7") (pinfunction "7_7") (pintype "passive"))
    )
    (net (code "30") (name "/IO6_PLAT") (class "Default")
      (node (ref "R319") (pin "2") (pinfunction "2_2") (pintype "passive"))
      (node (ref "S301") (pin "10") (pinfunction "10_10") (pintype "passive"))
    )
    (net (code "31") (name "/IO7_DUT") (class "Default")
      (node (ref "R316") (pin "1") (pinfunction "1_1") (pintype "passive"))
      (node (ref "R317") (pin "1") (pinfunction "1_1") (pintype "passive"))
      (node (ref "S300") (pin "8") (pinfunction "8_8") (pintype "passive"))
      (node (ref "S301") (pin "8") (pinfunction "8_8") (pintype "passive"))
    )
    (net (code "32") (name "/IO7_PLAT") (class "Default")
      (node (ref "R317") (pin "2") (pinfunction "2_2") (pintype "passive"))
      (node (ref "S301") (pin "9") (pinfunction "9_9") (pintype "passive"))
    )
    (net (code "33") (name "/IO8_DUT") (class "Default")
      (node (ref "R334") (pin "1") (pinfunction "1_1") (pintype "passive"))
      (node (ref "R335") (pin "1") (pinfunction "1_1") (pintype "passive"))
      (node (ref "S302") (pin "1") (pinfunction "1_1") (pintype "passive"))
      (node (ref "S303") (pin "1") (pinfunction "1_1") (pintype "passive"))
    )
    (net (code "34") (name "/IO8_PLAT") (class "Default")
      (node (ref "R335") (pin "2") (pinfunction "2_2") (pintype "passive"))
      (node (ref "S303") (pin "16") (pinfunction "16_16") (pintype "passive"))
    )
    (net (code "35") (name "/IO9_DUT") (class "Default")
      (node (ref "R332") (pin "1") (pinfunction "1_1") (pintype "passive"))
      (node (ref "R333") (pin "1") (pinfunction "1_1") (pintype "passive"))
      (node (ref "S302") (pin "2") (pinfunction "2_2") (pintype "passive"))
      (node (ref "S303") (pin "2") (pinfunction "2_2") (pintype "passive"))
    )
    (net (code "36") (name "/IO9_PLAT") (class "Default")
      (node (ref "R333") (pin "2") (pinfunction "2_2") (pintype "passive"))
      (node (ref "S303") (pin "15") (pinfunction "15_15") (pintype "passive"))
    )
    (net (code "37") (name "/IO10_DUT") (class "Default")
      (node (ref "R330") (pin "1") (pinfunction "1_1") (pintype "passive"))
      (node (ref "R331") (pin "1") (pinfunction "1_1") (pintype "passive"))
      (node (ref "S302") (pin "3") (pinfunction "3_3") (pintype "passive"))
      (node (ref "S303") (pin "3") (pinfunction "3_3") (pintype "passive"))
    )
    (net (code "38") (name "/IO10_PLAT") (class "Default")
      (node (ref "R331") (pin "2") (pinfunction "2_2") (pintype "passive"))
      (node (ref "S303") (pin "14") (pinfunction "14_14") (pintype "passive"))
    )
    (net (code "39") (name "/IO11_DUT") (class "Default")
      (node (ref "R326") (pin "1") (pinfunction "1_1") (pintype "passive"))
      (node (ref "R327") (pin "1") (pinfunction "1_1") (pintype "passive"))
      (node (ref "S302") (pin "4") (pinfunction "4_4") (pintype "passive"))
      (node (ref "S303") (pin "4") (pinfunction "4_4") (pintype "passive"))
    )
    (net (code "40") (name "/IO11_PLAT") (class "Default")
      (node (ref "R327") (pin "2") (pinfunction "2_2") (pintype "passive"))
      (node (ref "S303") (pin "13") (pinfunction "13_13") (pintype "passive"))
    )
    (net (code "41") (name "/IO12_DUT") (class "Default")
      (node (ref "R350") (pin "1") (pinfunction "1_1") (pintype "passive"))
      (node (ref "R351") (pin "1") (pinfunction "1_1") (pintype "passive"))
      (node (ref "S302") (pin "5") (pinfunction "5_5") (pintype "passive"))
      (node (ref "S303") (pin "5") (pinfunction "5_5") (pintype "passive"))
    )
    (net (code "42") (name "/IO12_PLAT") (class "Default")
      (node (ref "R351") (pin "2") (pinfunction "2_2") (pintype "passive"))
      (node (ref "S303") (pin "12") (pinfunction "12_12") (pintype "passive"))
    )
    (net (code "43") (name "/IO13_DUT") (class "Default")
      (node (ref "R346") (pin "1") (pinfunction "1_1") (pintype "passive"))
      (node (ref "R347") (pin "1") (pinfunction "1_1") (pintype "passive"))
      (node (ref "S302") (pin "6") (pinfunction "6_6") (pintype "passive"))
      (node (ref "S303") (pin "6") (pinfunction "6_6") (pintype "passive"))
    )
    (net (code "44") (name "/IO13_PLAT") (class "Default")
      (node (ref "R347") (pin "2") (pinfunction "2_2") (pintype "passive"))
      (node (ref "S303") (pin "11") (pinfunction "11_11") (pintype "passive"))
    )
    (net (code "45") (name "/IO14_DUT") (class "Default")
      (node (ref "R342") (pin "1") (pinfunction "1_1") (pintype "passive"))
      (node (ref "R343") (pin "1") (pinfunction "1_1") (pintype "passive"))
      (node (ref "S302") (pin "7") (pinfunction "7_7") (pintype "passive"))
      (node (ref "S303") (pin "7") (pinfunction "7_7") (pintype "passive"))
    )
    (net (code "46") (name "/IO14_PLAT") (class "Default")
      (node (ref "R343") (pin "2") (pinfunction "2_2") (pintype "passive"))
      (node (ref "S303") (pin "10") (pinfunction "10_10") (pintype "passive"))
    )
    (net (code "47") (name "/IO15_DUT") (class "Default")
      (node (ref "R340") (pin "1") (pinfunction "1_1") (pintype "passive"))
      (node (ref "R341") (pin "1") (pinfunction "1_1") (pintype "passive"))
      (node (ref "S302") (pin "8") (pinfunction "8_8") (pintype "passive"))
      (node (ref "S303") (pin "8") (pinfunction "8_8") (pintype "passive"))
    )
    (net (code "48") (name "/IO15_PLAT") (class "Default")
      (node (ref "R341") (pin "2") (pinfunction "2_2") (pintype "passive"))
      (node (ref "S303") (pin "9") (pinfunction "9_9") (pintype "passive"))
    )
    (net (code "49") (name "/IO_SMA0") (class "Default")
      (node (ref "R344") (pin "1") (pinfunction "1_1") (pintype "passive"))
      (node (ref "R348") (pin "2") (pinfunction "2_2") (pintype "passive"))
    )
    (net (code "50") (name "/IO_SMA1") (class "Default")
      (node (ref "R345") (pin "1") (pinfunction "1_1") (pintype "passive"))
      (node (ref "R349") (pin "2") (pinfunction "2_2") (pintype "passive"))
    )
    (net (code "51") (name "/IO_SMA2") (class "Default")
      (node (ref "R336") (pin "1") (pinfunction "1_1") (pintype "passive"))
      (node (ref "R338") (pin "2") (pinfunction "2_2") (pintype "passive"))
    )
    (net (code "52") (name "/IO_SMA3") (class "Default")
      (node (ref "R337") (pin "1") (pinfunction "1_1") (pintype "passive"))
      (node (ref "R339") (pin "2") (pinfunction "2_2") (pintype "passive"))
    )
    (net (code "53") (name "/TEARING") (class "Default")
      (node (ref "R300") (pin "1") (pinfunction "1_1") (pintype "passive"))
      (node (ref "R301") (pin "2") (pinfunction "2_2") (pintype "passive"))
    )
    (net (code "54") (name "GND") (class "Default")
      (node (ref "CN300") (pin "2") (pinfunction "2_2") (pintype "passive"))
      (node (ref "CN300") (pin "3") (pinfunction "3_3") (pintype "passive"))
      (node (ref "CN301") (pin "2") (pinfunction "2_2") (pintype "passive"))
      (node (ref "CN301") (pin "3") (pinfunction "3_3") (pintype "passive"))
      (node (ref "CN302") (pin "2") (pinfunction "2_2") (pintype "passive"))
      (node (ref "CN302") (pin "3") (pinfunction "3_3") (pintype "passive"))
      (node (ref "CN303") (pin "2") (pinfunction "2_2") (pintype "passive"))
      (node (ref "CN303") (pin "3") (pinfunction "3_3") (pintype "passive"))
      (node (ref "CN304") (pin "2") (pinfunction "2_2") (pintype "passive"))
      (node (ref "CN304") (pin "3") (pinfunction "3_3") (pintype "passive"))
      (node (ref "CN305") (pin "2") (pinfunction "2_2") (pintype "passive"))
      (node (ref "CN305") (pin "3") (pinfunction "3_3") (pintype "passive"))
      (node (ref "CN306") (pin "2") (pinfunction "2_2") (pintype "passive"))
      (node (ref "CN306") (pin "3") (pinfunction "3_3") (pintype "passive"))
      (node (ref "CN309") (pin "2") (pinfunction "2_2") (pintype "passive"))
      (node (ref "CN309") (pin "3") (pinfunction "3_3") (pintype "passive"))
      (node (ref "CN310") (pin "2") (pinfunction "2_2") (pintype "passive"))
      (node (ref "CN310") (pin "3") (pinfunction "3_3") (pintype "passive"))
      (node (ref "CN311") (pin "2") (pinfunction "2_2") (pintype "passive"))
      (node (ref "CN311") (pin "3") (pinfunction "3_3") (pintype "passive"))
      (node (ref "CN312") (pin "2") (pinfunction "2_2") (pintype "passive"))
      (node (ref "CN312") (pin "3") (pinfunction "3_3") (pintype "passive"))
      (node (ref "R301") (pin "1") (pinfunction "1_1") (pintype "passive"))
      (node (ref "R338") (pin "1") (pinfunction "1_1") (pintype "passive"))
      (node (ref "R339") (pin "1") (pinfunction "1_1") (pintype "passive"))
      (node (ref "R348") (pin "1") (pinfunction "1_1") (pintype "passive"))
      (node (ref "R349") (pin "1") (pinfunction "1_1") (pintype "passive"))
    )
    (net (code "55") (name "Net-(CN300-Pad1)") (class "Default")
      (node (ref "CN300") (pin "1") (pinfunction "1_1") (pintype "passive"))
      (node (ref "R300") (pin "2") (pinfunction "2_2") (pintype "passive"))
      (node (ref "THP300") (pin "1") (pinfunction "1_1") (pintype "passive"))
    )
    (net (code "56") (name "Net-(CN301-Pad1)") (class "Default")
      (node (ref "CN301") (pin "1") (pinfunction "1_1") (pintype "passive"))
      (node (ref "R302") (pin "2") (pinfunction "2_2") (pintype "passive"))
      (node (ref "THP301") (pin "1") (pinfunction "1_1") (pintype "passive"))
    )
    (net (code "57") (name "Net-(CN302-Pad1)") (class "Default")
      (node (ref "CN302") (pin "1") (pinfunction "1_1") (pintype "passive"))
      (node (ref "R303") (pin "2") (pinfunction "2_2") (pintype "passive"))
      (node (ref "THP302") (pin "1") (pinfunction "1_1") (pintype "passive"))
    )
    (net (code "58") (name "Net-(CN303-Pad1)") (class "Default")
      (node (ref "CN303") (pin "1") (pinfunction "1_1") (pintype "passive"))
      (node (ref "R310") (pin "2") (pinfunction "2_2") (pintype "passive"))
      (node (ref "THP303") (pin "1") (pinfunction "1_1") (pintype "passive"))
    )
    (net (code "59") (name "Net-(CN304-Pad1)") (class "Default")
      (node (ref "CN304") (pin "1") (pinfunction "1_1") (pintype "passive"))
      (node (ref "R311") (pin "2") (pinfunction "2_2") (pintype "passive"))
      (node (ref "THP304") (pin "1") (pinfunction "1_1") (pintype "passive"))
    )
    (net (code "60") (name "Net-(CN305-Pad1)") (class "Default")
      (node (ref "CN305") (pin "1") (pinfunction "1_1") (pintype "passive"))
      (node (ref "R314") (pin "2") (pinfunction "2_2") (pintype "passive"))
      (node (ref "THP305") (pin "1") (pinfunction "1_1") (pintype "passive"))
    )
    (net (code "61") (name "Net-(CN306-Pad1)") (class "Default")
      (node (ref "CN306") (pin "1") (pinfunction "1_1") (pintype "passive"))
      (node (ref "R315") (pin "2") (pinfunction "2_2") (pintype "passive"))
      (node (ref "THP306") (pin "1") (pinfunction "1_1") (pintype "passive"))
    )
    (net (code "62") (name "Net-(CN309-Pad1)") (class "Default")
      (node (ref "CN309") (pin "1") (pinfunction "1_1") (pintype "passive"))
      (node (ref "R336") (pin "2") (pinfunction "2_2") (pintype "passive"))
      (node (ref "THP309") (pin "1") (pinfunction "1_1") (pintype "passive"))
    )
    (net (code "63") (name "Net-(CN310-Pad1)") (class "Default")
      (node (ref "CN310") (pin "1") (pinfunction "1_1") (pintype "passive"))
      (node (ref "R337") (pin "2") (pinfunction "2_2") (pintype "passive"))
      (node (ref "THP310") (pin "1") (pinfunction "1_1") (pintype "passive"))
    )
    (net (code "64") (name "Net-(CN311-Pad1)") (class "Default")
      (node (ref "CN311") (pin "1") (pinfunction "1_1") (pintype "passive"))
      (node (ref "R344") (pin "2") (pinfunction "2_2") (pintype "passive"))
      (node (ref "THP311") (pin "1") (pinfunction "1_1") (pintype "passive"))
    )
    (net (code "65") (name "Net-(CN312-Pad1)") (class "Default")
      (node (ref "CN312") (pin "1") (pinfunction "1_1") (pintype "passive"))
      (node (ref "R345") (pin "2") (pinfunction "2_2") (pintype "passive"))
      (node (ref "THP312") (pin "1") (pinfunction "1_1") (pintype "passive"))
    )
  )
)
